# swr-antenna.net
KiCad netlist of a schematic drawn in Altium Designer
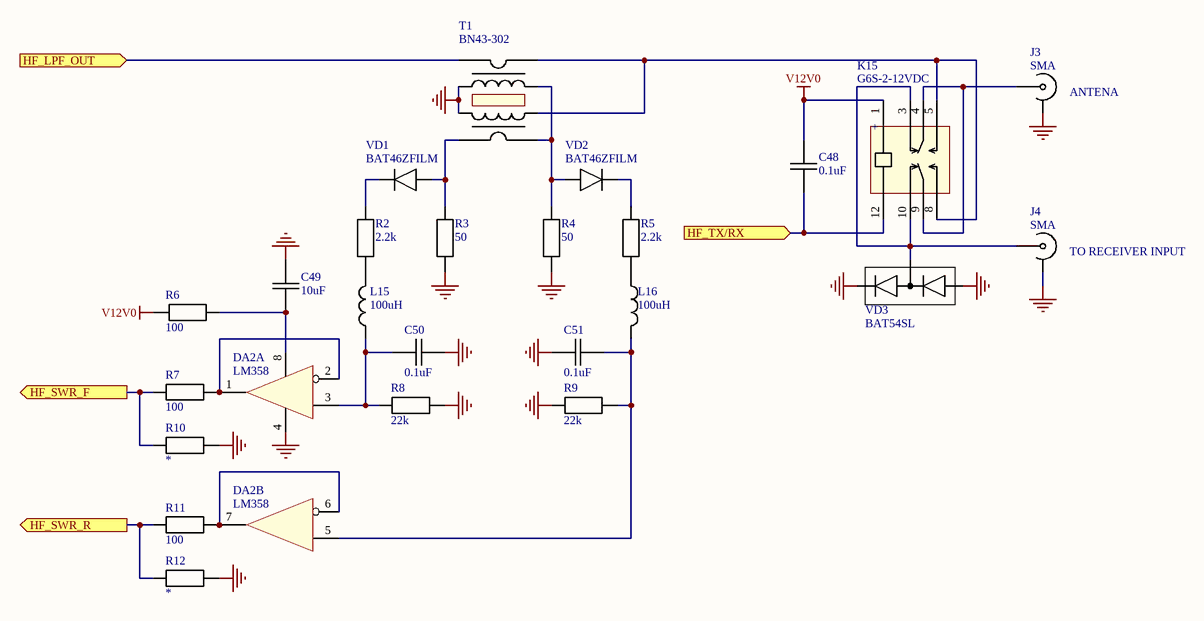
[diagram p0: swr-antenna.SchDoc]

(export (version "E")
  (design (tool "Eeschema 10.0.6"))
  (components
    (comp (ref "C48")
      (value "0.1uF")
      (footprint "CAPC2013X100N")
      (description "Capacitor 2x1.25 mm")
      (libsource (lib "common-lib") (part "Cap0805"))
    )
    (comp (ref "C49")
      (value "10uF")
      (footprint "CAPC2013X100N")
      (description "Capacitor 2x1.25 mm")
      (libsource (lib "common-lib") (part "Cap0805"))
    )
    (comp (ref "C50")
      (value "0.1uF")
      (footprint "CAPC2013X100N")
      (description "Capacitor 2x1.25 mm")
      (libsource (lib "common-lib") (part "Cap0805"))
    )
    (comp (ref "C51")
      (value "0.1uF")
      (footprint "CAPC2013X100N")
      (description "Capacitor 2x1.25 mm")
      (libsource (lib "common-lib") (part "Cap0805"))
    )
    (comp (ref "DA2")
      (value "LM358")
      (footprint "SOIC127P600X175-8N")
      (description "Single Supply Dual\r\nOperational Amplifiers")
      (libsource (lib "PALib") (part "LM358"))
    )
    (comp (ref "J3")
      (value "SMA")
      (footprint "SMA002")
      (description "EM-BC028M-NGP-50")
      (libsource (lib "PALib") (part "RF Connector"))
    )
    (comp (ref "J4") (value "SMA") (footprint "SMA002") (libsource (lib "PALib") (part "RF Connector")))
    (comp (ref "K15")
      (value "G6S-2-12VDC")
      (footprint "G6S-2")
      (description "Compact, Industry-Standard 2-pole relay")
      (libsource (lib "PALib") (part "G6S-2-12VDC"))
    )
    (comp (ref "L15")
      (value "100uH")
      (footprint "INDUCTOR-1008")
      (description "SWI1008HT101K-Hitano")
      (libsource (lib "PALib") (part "Inductor"))
    )
    (comp (ref "L16")
      (value "100uH")
      (footprint "INDUCTOR-1008")
      (description "SWI1008HT101K-Hitano")
      (libsource (lib "") (part "Inductor_1"))
    )
    (comp (ref "R2")
      (value "2.2k")
      (footprint "RESC2013X64N")
      (libsource (lib "common-lib") (part "Res0805"))
    )
    (comp (ref "R3") (value "50") (footprint "RESC2013X64N") (libsource (lib "common-lib") (part "Res0805")))
    (comp (ref "R4") (value "50") (footprint "RESC2013X64N") (libsource (lib "common-lib") (part "Res0805")))
    (comp (ref "R5")
      (value "2.2k")
      (footprint "RESC2013X64N")
      (libsource (lib "common-lib") (part "Res0805"))
    )
    (comp (ref "R6") (value "100") (footprint "RESC2013X64N") (libsource (lib "common-lib") (part "Res0805")))
    (comp (ref "R7") (value "100") (footprint "RESC2013X64N") (libsource (lib "common-lib") (part "Res0805")))
    (comp (ref "R8") (value "22k") (footprint "RESC2013X64N") (libsource (lib "common-lib") (part "Res0805")))
    (comp (ref "R9") (value "22k") (footprint "RESC2013X64N") (libsource (lib "common-lib") (part "Res0805")))
    (comp (ref "R10") (value "*") (footprint "RESC2013X64N") (libsource (lib "common-lib") (part "Res0805")))
    (comp (ref "R11")
      (value "100")
      (footprint "RESC2013X64N")
      (libsource (lib "common-lib") (part "Res0805"))
    )
    (comp (ref "R12") (value "*") (footprint "RESC2013X64N") (libsource (lib "common-lib") (part "Res0805")))
    (comp (ref "T1") (value "BN43-302") (footprint "TANDEM") (libsource (lib "PALib") (part "tandem match")))
    (comp (ref "VD1")
      (value "BAT46ZFILM")
      (footprint "SOD3816X118N")
      (description "Small signal Schottky diodes")
      (libsource (lib "PALib") (part "DIODE"))
    )
    (comp (ref "VD2")
      (value "BAT46ZFILM")
      (footprint "SOD3816X118N")
      (description "Small signal Schottky diodes")
      (libsource (lib "PALib") (part "DIODE"))
    )
    (comp (ref "VD3")
      (value "BAT54SL")
      (footprint "SOT95P229X119-3N")
      (libsource (lib "common-lib") (part "DIODE-2-1A-3C-3A-2C"))
    )
  )
  (nets
    (net (code "1") (name "/HF_LPF_OUT") (class "Default") (node (ref "T1") (pin "1") (pintype "passive")))
    (net (code "2") (name "/HF_SWR_F") (class "Default")
      (node (ref "R10") (pin "2") (pintype "passive"))
      (node (ref "R7") (pin "2") (pintype "passive"))
    )
    (net (code "3") (name "/HF_SWR_R") (class "Default")
      (node (ref "R11") (pin "2") (pintype "passive"))
      (node (ref "R12") (pin "2") (pintype "passive"))
    )
    (net (code "4") (name "/HF_TX{slash}RX") (class "Default")
      (node (ref "C48") (pin "1") (pintype "passive"))
      (node (ref "K15") (pin "12") (pintype "passive"))
    )
    (net (code "5") (name "GND") (class "Default")
      (node (ref "C49") (pin "1") (pintype "passive"))
      (node (ref "C50") (pin "2") (pintype "passive"))
      (node (ref "C51") (pin "1") (pintype "passive"))
      (node (ref "DA2") (pin "4") (pinfunction "GND_4") (pintype "passive"))
      (node (ref "J3") (pin "2") (pinfunction "GND_2") (pintype "passive"))
      (node (ref "J4") (pin "2") (pinfunction "GND_2") (pintype "passive"))
      (node (ref "R10") (pin "1") (pintype "passive"))
      (node (ref "R12") (pin "1") (pintype "passive"))
      (node (ref "R3") (pin "1") (pintype "passive"))
      (node (ref "R4") (pin "1") (pintype "passive"))
      (node (ref "R8") (pin "1") (pintype "passive"))
      (node (ref "R9") (pin "2") (pintype "passive"))
      (node (ref "T1") (pin "3") (pintype "passive"))
      (node (ref "T1") (pin "5") (pintype "passive"))
      (node (ref "VD3") (pin "1") (pinfunction "A_1") (pintype "passive"))
      (node (ref "VD3") (pin "2") (pinfunction "C_2") (pintype "passive"))
    )
    (net (code "6") (name "Net-(DA2A-IN1+)") (class "Default")
      (node (ref "C50") (pin "1") (pintype "passive"))
      (node (ref "DA2") (pin "3") (pinfunction "IN1+_3") (pintype "passive"))
      (node (ref "L15") (pin "1") (pintype "passive"))
      (node (ref "R8") (pin "2") (pintype "passive"))
    )
    (net (code "7") (name "Net-(DA2A-IN1-)") (class "Default")
      (node (ref "DA2") (pin "1") (pinfunction "OUT1_1") (pintype "passive"))
      (node (ref "DA2") (pin "2") (pinfunction "IN1-_2") (pintype "passive"))
      (node (ref "R7") (pin "1") (pintype "passive"))
    )
    (net (code "8") (name "Net-(DA2A-VCC)") (class "Default")
      (node (ref "C49") (pin "2") (pintype "passive"))
      (node (ref "DA2") (pin "8") (pinfunction "VCC_8") (pintype "passive"))
      (node (ref "R6") (pin "2") (pintype "passive"))
    )
    (net (code "9") (name "Net-(DA2B-IN2+)") (class "Default")
      (node (ref "C51") (pin "2") (pintype "passive"))
      (node (ref "DA2") (pin "5") (pinfunction "IN2+_5") (pintype "passive"))
      (node (ref "L16") (pin "2") (pintype "passive"))
      (node (ref "R9") (pin "1") (pintype "passive"))
    )
    (net (code "10") (name "Net-(DA2B-IN2-)") (class "Default")
      (node (ref "DA2") (pin "6") (pinfunction "IN2-_6") (pintype "passive"))
      (node (ref "DA2") (pin "7") (pinfunction "OUT2_7") (pintype "passive"))
      (node (ref "R11") (pin "1") (pintype "passive"))
    )
    (net (code "11") (name "Net-(J3-RF)") (class "Default")
      (node (ref "J3") (pin "1") (pinfunction "RF_1") (pintype "passive"))
      (node (ref "K15") (pin "4") (pintype "passive"))
      (node (ref "K15") (pin "9") (pintype "passive"))
    )
    (net (code "12") (name "Net-(J4-RF)") (class "Default")
      (node (ref "J4") (pin "1") (pinfunction "RF_1") (pintype "passive"))
      (node (ref "K15") (pin "10") (pintype "passive"))
      (node (ref "K15") (pin "3") (pintype "passive"))
      (node (ref "VD3") (pin "3") (pinfunction "AC_3") (pintype "passive"))
    )
    (net (code "13") (name "Net-(K15-Pad5)") (class "Default")
      (node (ref "K15") (pin "5") (pintype "passive"))
      (node (ref "K15") (pin "8") (pintype "passive"))
      (node (ref "T1") (pin "2") (pintype "passive"))
      (node (ref "T1") (pin "6") (pintype "passive"))
    )
    (net (code "14") (name "Net-(L15-Pad2)") (class "Default")
      (node (ref "L15") (pin "2") (pintype "passive"))
      (node (ref "R2") (pin "1") (pintype "passive"))
    )
    (net (code "15") (name "Net-(L16-Pad1)") (class "Default")
      (node (ref "L16") (pin "1") (pintype "passive"))
      (node (ref "R5") (pin "1") (pintype "passive"))
    )
    (net (code "16") (name "Net-(VD1-A)") (class "Default")
      (node (ref "R3") (pin "2") (pintype "passive"))
      (node (ref "T1") (pin "7") (pintype "passive"))
      (node (ref "VD1") (pin "2") (pinfunction "A_2") (pintype "passive"))
    )
    (net (code "17") (name "Net-(VD1-C)") (class "Default")
      (node (ref "R2") (pin "2") (pintype "passive"))
      (node (ref "VD1") (pin "1") (pinfunction "C_1") (pintype "passive"))
    )
    (net (code "18") (name "Net-(VD2-A)") (class "Default")
      (node (ref "R4") (pin "2") (pintype "passive"))
      (node (ref "T1") (pin "4") (pintype "passive"))
      (node (ref "T1") (pin "8") (pintype "passive"))
      (node (ref "VD2") (pin "2") (pinfunction "A_2") (pintype "passive"))
    )
    (net (code "19") (name "Net-(VD2-C)") (class "Default")
      (node (ref "R5") (pin "2") (pintype "passive"))
      (node (ref "VD2") (pin "1") (pinfunction "C_1") (pintype "passive"))
    )
    (net (code "20") (name "V12V0") (class "Default")
      (node (ref "C48") (pin "2") (pintype "passive"))
      (node (ref "K15") (pin "1") (pintype "passive"))
      (node (ref "R6") (pin "1") (pintype "passive"))
    )
  )
)
